# COVERsation_v0_3.net
KiCad netlist of a schematic drawn in EAGLE
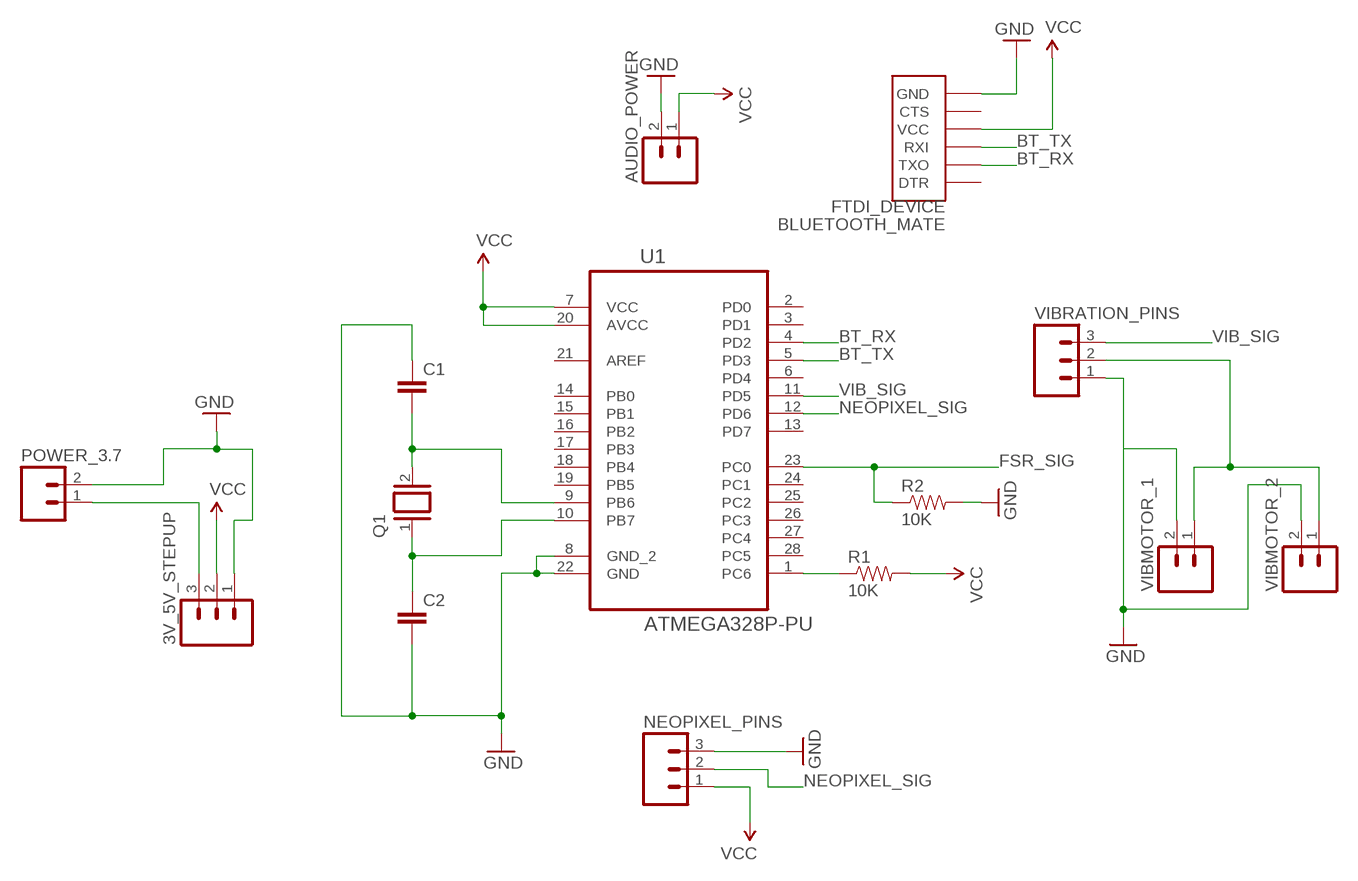
[diagram p0: schematic, sheet 1]

(export (version "E")
  (design (tool "Eeschema 10.0.6"))
  (components
    (comp (ref "3V_5V_STEPUP")
      (value "M03PTH")
      (footprint "eagle-import:1X03")
      (libsource (lib "eagle-import") (part "M03PTH"))
    )
    (comp (ref "AUDIO_POWER")
      (value "M02PTH")
      (footprint "eagle-import:1X02")
      (libsource (lib "eagle-import") (part "M02PTH"))
    )
    (comp (ref "BLUETOOTH_MATE")
      (value "FTDI_DEVICE")
      (footprint "eagle-import:FTDI_DEVICE_SIDE")
      (libsource (lib "eagle-import") (part "FTDI_DEVICE"))
    )
    (comp (ref "C1")
      (value "CAPPTH1")
      (footprint "eagle-import:CAP-PTH-5MM")
      (libsource (lib "eagle-import") (part "CAPPTH1"))
    )
    (comp (ref "C2")
      (value "CAPPTH1")
      (footprint "eagle-import:CAP-PTH-5MM")
      (libsource (lib "eagle-import") (part "CAPPTH1"))
    )
    (comp (ref "NEOPIXEL_PINS")
      (value "M03PTH")
      (footprint "eagle-import:1X03")
      (libsource (lib "eagle-import") (part "M03PTH"))
    )
    (comp (ref "POWER_3.7")
      (value "M02PTH")
      (footprint "eagle-import:1X02")
      (libsource (lib "eagle-import") (part "M02PTH"))
    )
    (comp (ref "Q1")
      (value "XTAL")
      (footprint "eagle-import:Q")
      (libsource (lib "eagle-import") (part "XTAL"))
    )
    (comp (ref "R1")
      (value "10K")
      (footprint "eagle-import:AXIAL-0.3EZ")
      (libsource (lib "eagle-import") (part "RESISTOREZ"))
    )
    (comp (ref "R2")
      (value "10K")
      (footprint "eagle-import:AXIAL-0.3EZ")
      (libsource (lib "eagle-import") (part "RESISTOREZ"))
    )
    (comp (ref "U1")
      (value "ATMEGA328P-PU")
      (footprint "eagle-import:DIP254P762X457-28")
      (libsource (lib "eagle-import") (part "ATMEGA328P-PU"))
    )
    (comp (ref "VIBMOTOR_1")
      (value "M02PTH")
      (footprint "eagle-import:1X02")
      (libsource (lib "eagle-import") (part "M02PTH"))
    )
    (comp (ref "VIBMOTOR_2")
      (value "M02PTH")
      (footprint "eagle-import:1X02")
      (libsource (lib "eagle-import") (part "M02PTH"))
    )
    (comp (ref "VIBRATION_PINS")
      (value "M03PTH")
      (footprint "eagle-import:1X03")
      (libsource (lib "eagle-import") (part "M03PTH"))
    )
  )
  (nets
    (net (code "1") (name "/BT_RX") (class "Default")
      (node (ref "BLUETOOTH_MATE") (pin "P$2") (pinfunction "TXO_P$2") (pintype "bidirectional"))
      (node (ref "U1") (pin "4") (pinfunction "PD2_4") (pintype "bidirectional"))
    )
    (net (code "2") (name "/BT_TX") (class "Default")
      (node (ref "BLUETOOTH_MATE") (pin "P$3") (pinfunction "RXI_P$3") (pintype "bidirectional"))
      (node (ref "U1") (pin "5") (pinfunction "PD3_5") (pintype "bidirectional"))
    )
    (net (code "3") (name "/FSR_SIG") (class "Default")
      (node (ref "R2") (pin "P$1") (pinfunction "1_P$1") (pintype "passive"))
      (node (ref "U1") (pin "23") (pinfunction "PC0_23") (pintype "bidirectional"))
    )
    (net (code "4") (name "/NEOPIXEL_SIG") (class "Default")
      (node (ref "NEOPIXEL_PINS") (pin "2") (pinfunction "2_2") (pintype "passive"))
      (node (ref "U1") (pin "12") (pinfunction "PD6_12") (pintype "bidirectional"))
    )
    (net (code "5") (name "/VIB_SIG") (class "Default")
      (node (ref "U1") (pin "11") (pinfunction "PD5_11") (pintype "bidirectional"))
      (node (ref "VIBRATION_PINS") (pin "3") (pinfunction "3_3") (pintype "passive"))
    )
    (net (code "6") (name "GND") (class "Default")
      (node (ref "3V_5V_STEPUP") (pin "1") (pinfunction "1_1") (pintype "passive"))
      (node (ref "AUDIO_POWER") (pin "2") (pinfunction "2_2") (pintype "passive"))
      (node (ref "BLUETOOTH_MATE") (pin "P$6") (pinfunction "GND_P$6") (pintype "bidirectional"))
      (node (ref "C1") (pin "1") (pinfunction "1_1") (pintype "passive"))
      (node (ref "C2") (pin "2") (pinfunction "2_2") (pintype "passive"))
      (node (ref "NEOPIXEL_PINS") (pin "3") (pinfunction "3_3") (pintype "passive"))
      (node (ref "POWER_3.7") (pin "2") (pinfunction "2_2") (pintype "passive"))
      (node (ref "R2") (pin "P$2") (pinfunction "2_P$2") (pintype "passive"))
      (node (ref "U1") (pin "22") (pinfunction "GND_22") (pintype "passive"))
      (node (ref "U1") (pin "8") (pinfunction "GND_2_8") (pintype "passive"))
      (node (ref "VIBMOTOR_1") (pin "2") (pinfunction "2_2") (pintype "passive"))
      (node (ref "VIBMOTOR_2") (pin "2") (pinfunction "2_2") (pintype "passive"))
      (node (ref "VIBRATION_PINS") (pin "1") (pinfunction "1_1") (pintype "passive"))
    )
    (net (code "7") (name "Net-(3V_5V_STEPUP-Pad3)") (class "Default")
      (node (ref "3V_5V_STEPUP") (pin "3") (pinfunction "3_3") (pintype "passive"))
      (node (ref "POWER_3.7") (pin "1") (pinfunction "1_1") (pintype "passive"))
    )
    (net (code "8") (name "Net-(R1-1)") (class "Default")
      (node (ref "R1") (pin "P$1") (pinfunction "1_P$1") (pintype "passive"))
      (node (ref "U1") (pin "1") (pinfunction "PC6_1") (pintype "bidirectional"))
    )
    (net (code "9") (name "Net-(U1-PB6)") (class "Default")
      (node (ref "C1") (pin "2") (pinfunction "2_2") (pintype "passive"))
      (node (ref "Q1") (pin "2") (pinfunction "2_2") (pintype "passive"))
      (node (ref "U1") (pin "9") (pinfunction "PB6_9") (pintype "bidirectional"))
    )
    (net (code "10") (name "Net-(U1-PB7)") (class "Default")
      (node (ref "C2") (pin "1") (pinfunction "1_1") (pintype "passive"))
      (node (ref "Q1") (pin "1") (pinfunction "1_1") (pintype "passive"))
      (node (ref "U1") (pin "10") (pinfunction "PB7_10") (pintype "bidirectional"))
    )
    (net (code "11") (name "Net-(VIBMOTOR_1-Pad1)") (class "Default")
      (node (ref "VIBMOTOR_1") (pin "1") (pinfunction "1_1") (pintype "passive"))
      (node (ref "VIBMOTOR_2") (pin "1") (pinfunction "1_1") (pintype "passive"))
      (node (ref "VIBRATION_PINS") (pin "2") (pinfunction "2_2") (pintype "passive"))
    )
    (net (code "12") (name "VCC") (class "Default")
      (node (ref "3V_5V_STEPUP") (pin "2") (pinfunction "2_2") (pintype "passive"))
      (node (ref "AUDIO_POWER") (pin "1") (pinfunction "1_1") (pintype "passive"))
      (node (ref "BLUETOOTH_MATE") (pin "P$4") (pinfunction "VCC_P$4") (pintype "bidirectional"))
      (node (ref "NEOPIXEL_PINS") (pin "1") (pinfunction "1_1") (pintype "passive"))
      (node (ref "R1") (pin "P$2") (pinfunction "2_P$2") (pintype "passive"))
      (node (ref "U1") (pin "20") (pinfunction "AVCC_20") (pintype "power_in"))
      (node (ref "U1") (pin "7") (pinfunction "VCC_7") (pintype "power_in"))
    )
    (net (code "13") (name "unconnected-(BLUETOOTH_MATE-CTS-PadP$5)") (class "Default")
      (node (ref "BLUETOOTH_MATE") (pin "P$5") (pinfunction "CTS_P$5") (pintype "bidirectional"))
    )
    (net (code "14") (name "unconnected-(BLUETOOTH_MATE-DTR-PadP$1)") (class "Default")
      (node (ref "BLUETOOTH_MATE") (pin "P$1") (pinfunction "DTR_P$1") (pintype "bidirectional"))
    )
    (net (code "15") (name "unconnected-(U1-AREF-Pad21)") (class "Default")
      (node (ref "U1") (pin "21") (pinfunction "AREF_21") (pintype "input"))
    )
    (net (code "16") (name "unconnected-(U1-PB0-Pad14)") (class "Default")
      (node (ref "U1") (pin "14") (pinfunction "PB0_14") (pintype "bidirectional"))
    )
    (net (code "17") (name "unconnected-(U1-PB1-Pad15)") (class "Default")
      (node (ref "U1") (pin "15") (pinfunction "PB1_15") (pintype "bidirectional"))
    )
    (net (code "18") (name "unconnected-(U1-PB2-Pad16)") (class "Default")
      (node (ref "U1") (pin "16") (pinfunction "PB2_16") (pintype "bidirectional"))
    )
    (net (code "19") (name "unconnected-(U1-PB3-Pad17)") (class "Default")
      (node (ref "U1") (pin "17") (pinfunction "PB3_17") (pintype "bidirectional"))
    )
    (net (code "20") (name "unconnected-(U1-PB4-Pad18)") (class "Default")
      (node (ref "U1") (pin "18") (pinfunction "PB4_18") (pintype "bidirectional"))
    )
    (net (code "21") (name "unconnected-(U1-PB5-Pad19)") (class "Default")
      (node (ref "U1") (pin "19") (pinfunction "PB5_19") (pintype "bidirectional"))
    )
    (net (code "22") (name "unconnected-(U1-PC1-Pad24)") (class "Default")
      (node (ref "U1") (pin "24") (pinfunction "PC1_24") (pintype "bidirectional"))
    )
    (net (code "23") (name "unconnected-(U1-PC2-Pad25)") (class "Default")
      (node (ref "U1") (pin "25") (pinfunction "PC2_25") (pintype "bidirectional"))
    )
    (net (code "24") (name "unconnected-(U1-PC3-Pad26)") (class "Default")
      (node (ref "U1") (pin "26") (pinfunction "PC3_26") (pintype "bidirectional"))
    )
    (net (code "25") (name "unconnected-(U1-PC4-Pad27)") (class "Default")
      (node (ref "U1") (pin "27") (pinfunction "PC4_27") (pintype "bidirectional"))
    )
    (net (code "26") (name "unconnected-(U1-PC5-Pad28)") (class "Default")
      (node (ref "U1") (pin "28") (pinfunction "PC5_28") (pintype "bidirectional"))
    )
    (net (code "27") (name "unconnected-(U1-PD0-Pad2)") (class "Default")
      (node (ref "U1") (pin "2") (pinfunction "PD0_2") (pintype "bidirectional"))
    )
    (net (code "28") (name "unconnected-(U1-PD1-Pad3)") (class "Default")
      (node (ref "U1") (pin "3") (pinfunction "PD1_3") (pintype "bidirectional"))
    )
    (net (code "29") (name "unconnected-(U1-PD4-Pad6)") (class "Default")
      (node (ref "U1") (pin "6") (pinfunction "PD4_6") (pintype "bidirectional"))
    )
    (net (code "30") (name "unconnected-(U1-PD7-Pad13)") (class "Default")
      (node (ref "U1") (pin "13") (pinfunction "PD7_13") (pintype "bidirectional"))
    )
  )
)
